# mux-board.net
KiCad netlist of a schematic drawn in EAGLE
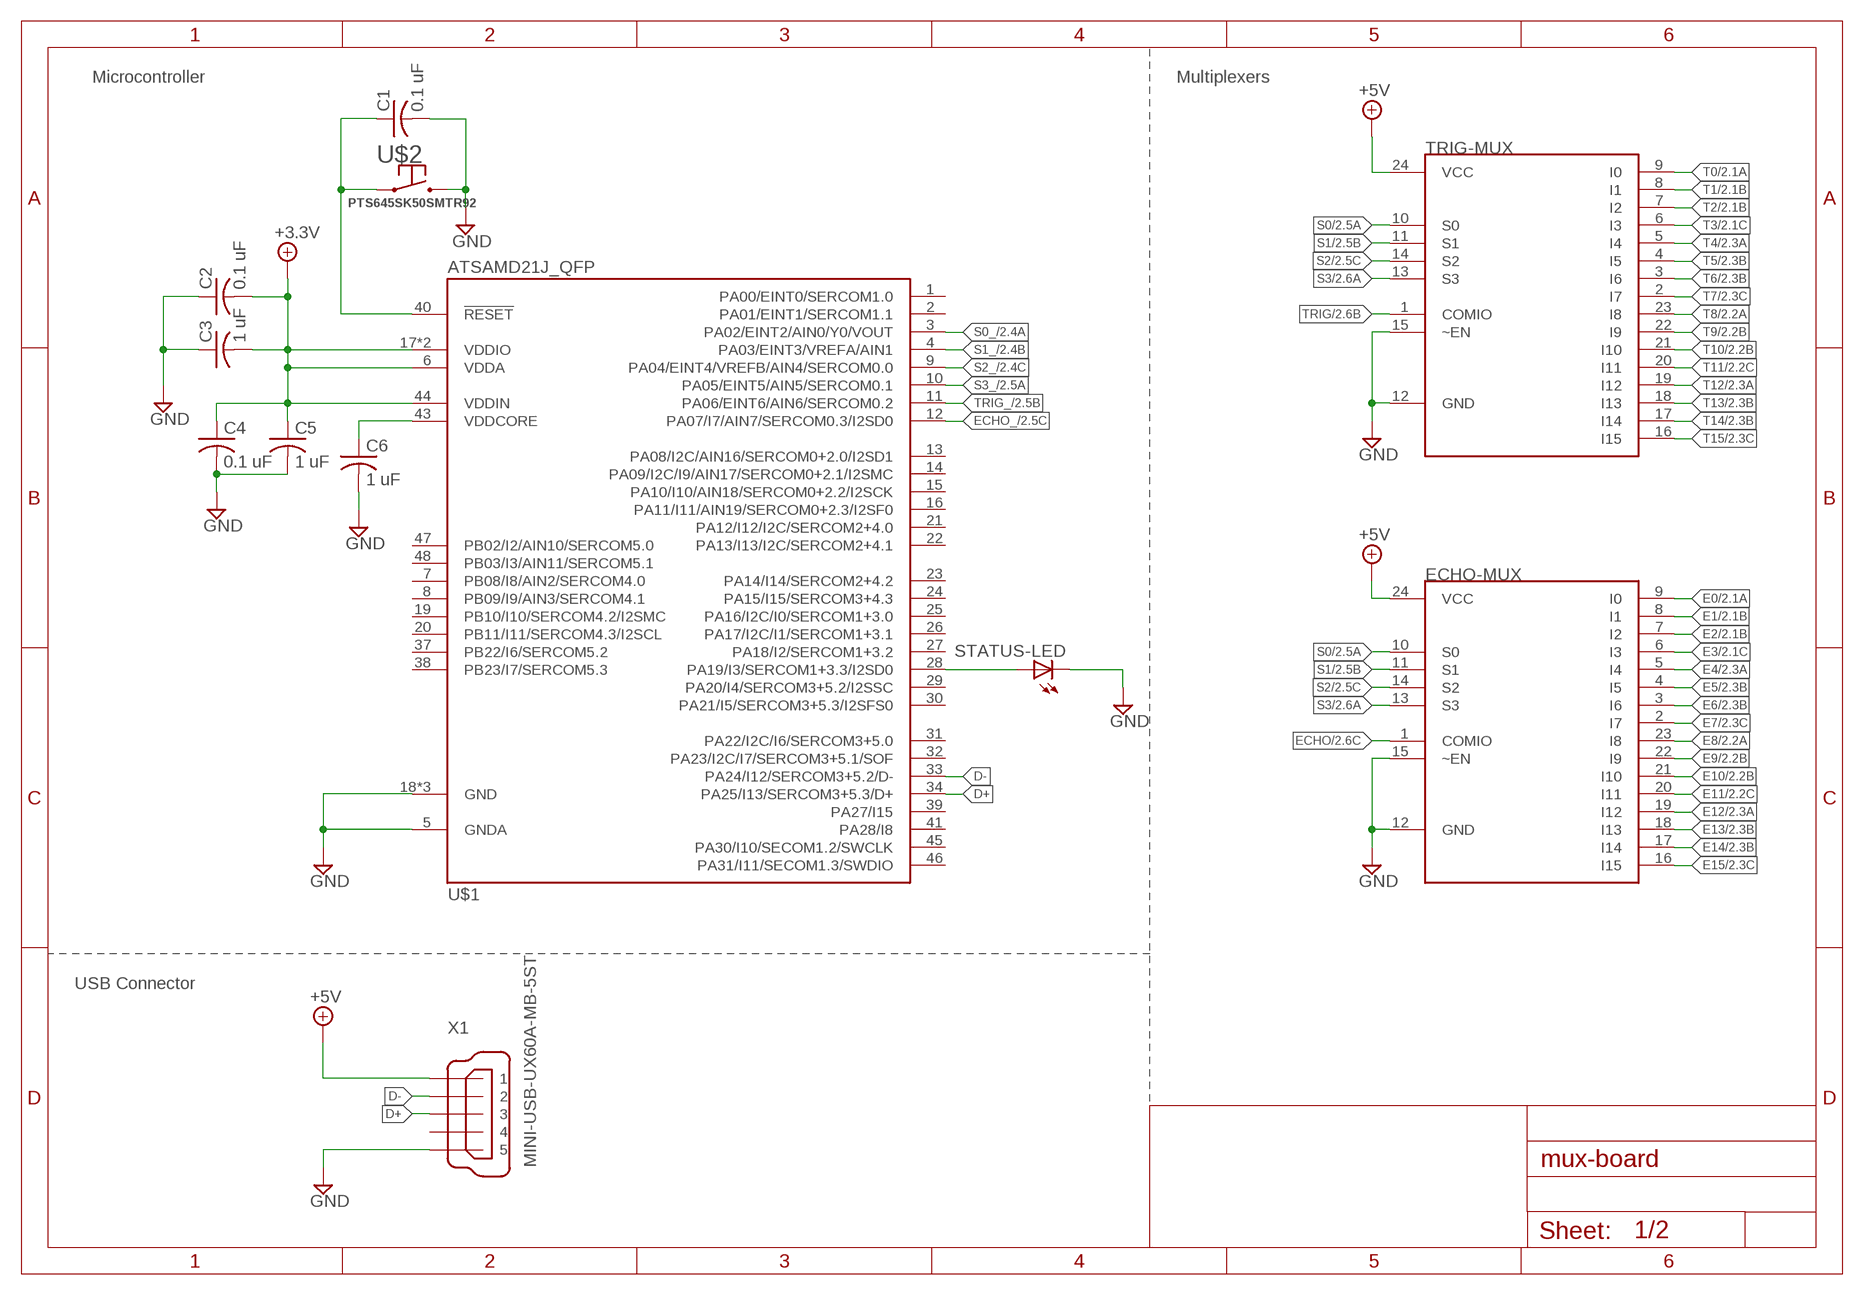
[diagram p0: schematic, sheet 1]
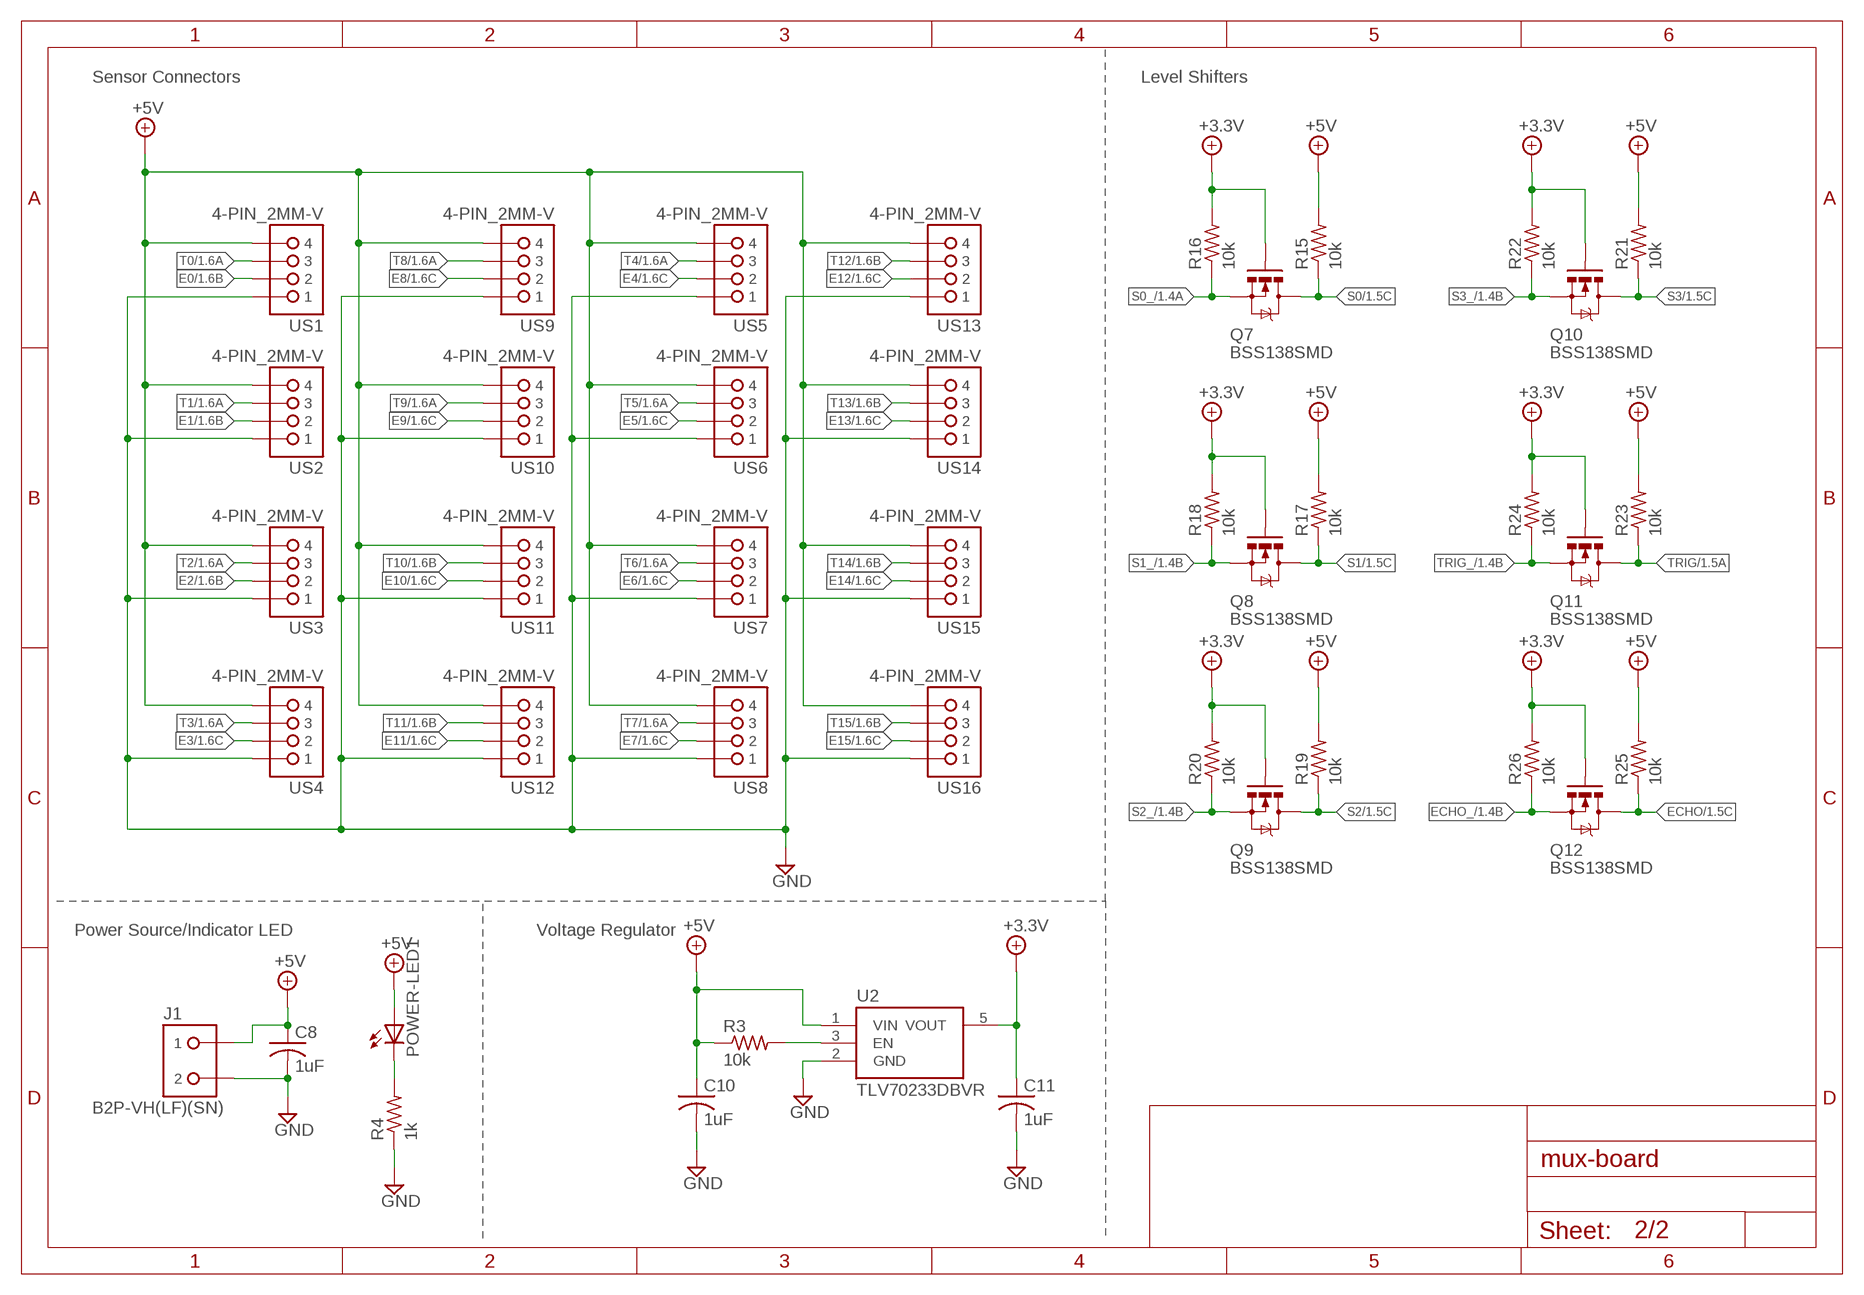
[diagram p1: schematic, sheet 2]

(export (version "E")
  (design (tool "Eeschema 10.0.6"))
  (components
    (comp (ref "C8")
      (value "1uF")
      (footprint "eagle-import:C0603")
      (libsource (lib "eagle-import") (part "C-USC0603"))
    )
    (comp (ref "C10")
      (value "1uF")
      (footprint "eagle-import:C0603")
      (libsource (lib "eagle-import") (part "C-USC0603"))
    )
    (comp (ref "C11")
      (value "1uF")
      (footprint "eagle-import:C0603")
      (libsource (lib "eagle-import") (part "C-USC0603"))
    )
    (comp (ref "J1")
      (value "B2P-VH(LF)(SN)")
      (footprint "eagle-import:B2P")
      (libsource (lib "eagle-import") (part "B2P?-VH(LF)(SN)"))
    )
    (comp (ref "POWER-LED1")
      (value "LEDSML0603")
      (footprint "eagle-import:SML0603")
      (libsource (lib "eagle-import") (part "LEDSML0603"))
    )
    (comp (ref "Q7")
      (value "BSS138SMD")
      (footprint "eagle-import:SPARKFUN_SOT23-3")
      (libsource (lib "eagle-import") (part "BSS138SMD"))
    )
    (comp (ref "Q8")
      (value "BSS138SMD")
      (footprint "eagle-import:SPARKFUN_SOT23-3")
      (libsource (lib "eagle-import") (part "BSS138SMD"))
    )
    (comp (ref "Q9")
      (value "BSS138SMD")
      (footprint "eagle-import:SPARKFUN_SOT23-3")
      (libsource (lib "eagle-import") (part "BSS138SMD"))
    )
    (comp (ref "Q10")
      (value "BSS138SMD")
      (footprint "eagle-import:SPARKFUN_SOT23-3")
      (libsource (lib "eagle-import") (part "BSS138SMD"))
    )
    (comp (ref "Q11")
      (value "BSS138SMD")
      (footprint "eagle-import:SPARKFUN_SOT23-3")
      (libsource (lib "eagle-import") (part "BSS138SMD"))
    )
    (comp (ref "Q12")
      (value "BSS138SMD")
      (footprint "eagle-import:SPARKFUN_SOT23-3")
      (libsource (lib "eagle-import") (part "BSS138SMD"))
    )
    (comp (ref "R3")
      (value "10k")
      (footprint "eagle-import:R0603")
      (libsource (lib "eagle-import") (part "resistor_348_R-US_R0603"))
    )
    (comp (ref "R4")
      (value "1k")
      (footprint "eagle-import:R0603")
      (libsource (lib "eagle-import") (part "resistor_348_R-US_R0603"))
    )
    (comp (ref "R15")
      (value "10k")
      (footprint "eagle-import:R0603")
      (libsource (lib "eagle-import") (part "R-US_R0603"))
    )
    (comp (ref "R16")
      (value "10k")
      (footprint "eagle-import:R0603")
      (libsource (lib "eagle-import") (part "R-US_R0603"))
    )
    (comp (ref "R17")
      (value "10k")
      (footprint "eagle-import:R0603")
      (libsource (lib "eagle-import") (part "R-US_R0603"))
    )
    (comp (ref "R18")
      (value "10k")
      (footprint "eagle-import:R0603")
      (libsource (lib "eagle-import") (part "R-US_R0603"))
    )
    (comp (ref "R19")
      (value "10k")
      (footprint "eagle-import:R0603")
      (libsource (lib "eagle-import") (part "R-US_R0603"))
    )
    (comp (ref "R20")
      (value "10k")
      (footprint "eagle-import:R0603")
      (libsource (lib "eagle-import") (part "R-US_R0603"))
    )
    (comp (ref "R21")
      (value "10k")
      (footprint "eagle-import:R0603")
      (libsource (lib "eagle-import") (part "R-US_R0603"))
    )
    (comp (ref "R22")
      (value "10k")
      (footprint "eagle-import:R0603")
      (libsource (lib "eagle-import") (part "R-US_R0603"))
    )
    (comp (ref "R23")
      (value "10k")
      (footprint "eagle-import:R0603")
      (libsource (lib "eagle-import") (part "R-US_R0603"))
    )
    (comp (ref "R24")
      (value "10k")
      (footprint "eagle-import:R0603")
      (libsource (lib "eagle-import") (part "R-US_R0603"))
    )
    (comp (ref "R25")
      (value "10k")
      (footprint "eagle-import:R0603")
      (libsource (lib "eagle-import") (part "R-US_R0603"))
    )
    (comp (ref "R26")
      (value "10k")
      (footprint "eagle-import:R0603")
      (libsource (lib "eagle-import") (part "R-US_R0603"))
    )
    (comp (ref "U2")
      (value "TLV70233DBVR")
      (footprint "eagle-import:SOT-23-5")
      (libsource (lib "eagle-import") (part "TLV70233DBVR"))
    )
    (comp (ref "US1")
      (value "4-PIN_2MM-V")
      (footprint "eagle-import:2MM-4-V")
      (libsource (lib "eagle-import") (part "4-PIN_2MM-V"))
    )
    (comp (ref "US2")
      (value "4-PIN_2MM-V")
      (footprint "eagle-import:2MM-4-V")
      (libsource (lib "eagle-import") (part "4-PIN_2MM-V"))
    )
    (comp (ref "US3")
      (value "4-PIN_2MM-V")
      (footprint "eagle-import:2MM-4-V")
      (libsource (lib "eagle-import") (part "4-PIN_2MM-V"))
    )
    (comp (ref "US4")
      (value "4-PIN_2MM-V")
      (footprint "eagle-import:2MM-4-V")
      (libsource (lib "eagle-import") (part "4-PIN_2MM-V"))
    )
    (comp (ref "US5")
      (value "4-PIN_2MM-V")
      (footprint "eagle-import:2MM-4-V")
      (libsource (lib "eagle-import") (part "4-PIN_2MM-V"))
    )
    (comp (ref "US6")
      (value "4-PIN_2MM-V")
      (footprint "eagle-import:2MM-4-V")
      (libsource (lib "eagle-import") (part "4-PIN_2MM-V"))
    )
    (comp (ref "US7")
      (value "4-PIN_2MM-V")
      (footprint "eagle-import:2MM-4-V")
      (libsource (lib "eagle-import") (part "4-PIN_2MM-V"))
    )
    (comp (ref "US8")
      (value "4-PIN_2MM-V")
      (footprint "eagle-import:2MM-4-V")
      (libsource (lib "eagle-import") (part "4-PIN_2MM-V"))
    )
    (comp (ref "US9")
      (value "4-PIN_2MM-V")
      (footprint "eagle-import:2MM-4-V")
      (libsource (lib "eagle-import") (part "4-PIN_2MM-V"))
    )
    (comp (ref "US10")
      (value "4-PIN_2MM-V")
      (footprint "eagle-import:2MM-4-V")
      (libsource (lib "eagle-import") (part "4-PIN_2MM-V"))
    )
    (comp (ref "US11")
      (value "4-PIN_2MM-V")
      (footprint "eagle-import:2MM-4-V")
      (libsource (lib "eagle-import") (part "4-PIN_2MM-V"))
    )
    (comp (ref "US12")
      (value "4-PIN_2MM-V")
      (footprint "eagle-import:2MM-4-V")
      (libsource (lib "eagle-import") (part "4-PIN_2MM-V"))
    )
    (comp (ref "US13")
      (value "4-PIN_2MM-V")
      (footprint "eagle-import:2MM-4-V")
      (libsource (lib "eagle-import") (part "4-PIN_2MM-V"))
    )
    (comp (ref "US14")
      (value "4-PIN_2MM-V")
      (footprint "eagle-import:2MM-4-V")
      (libsource (lib "eagle-import") (part "4-PIN_2MM-V"))
    )
    (comp (ref "US15")
      (value "4-PIN_2MM-V")
      (footprint "eagle-import:2MM-4-V")
      (libsource (lib "eagle-import") (part "4-PIN_2MM-V"))
    )
    (comp (ref "US16")
      (value "4-PIN_2MM-V")
      (footprint "eagle-import:2MM-4-V")
      (libsource (lib "eagle-import") (part "4-PIN_2MM-V"))
    )
    (comp (ref "C1")
      (value "0.1 uF")
      (footprint "eagle-import:C0603")
      (libsource (lib "eagle-import") (part "resistor_348_C-USC0603"))
    )
    (comp (ref "C2")
      (value "0.1 uF")
      (footprint "eagle-import:C0603")
      (libsource (lib "eagle-import") (part "resistor_348_C-USC0603"))
    )
    (comp (ref "C3")
      (value "1 uF")
      (footprint "eagle-import:C0603")
      (libsource (lib "eagle-import") (part "resistor_348_C-USC0603"))
    )
    (comp (ref "C4")
      (value "0.1 uF")
      (footprint "eagle-import:C0603")
      (libsource (lib "eagle-import") (part "resistor_348_C-USC0603"))
    )
    (comp (ref "C5")
      (value "1 uF")
      (footprint "eagle-import:C0603")
      (libsource (lib "eagle-import") (part "resistor_348_C-USC0603"))
    )
    (comp (ref "C6")
      (value "1 uF")
      (footprint "eagle-import:C0603")
      (libsource (lib "eagle-import") (part "resistor_348_C-USC0603"))
    )
    (comp (ref "ECHO-MUX")
      (value "CD74HC4067")
      (footprint "eagle-import:SO24R")
      (libsource (lib "eagle-import") (part "CD74HC4067"))
    )
    (comp (ref "STATUS-LED")
      (value "LEDSML0603")
      (footprint "eagle-import:SML0603")
      (libsource (lib "eagle-import") (part "LEDSML0603"))
    )
    (comp (ref "TRIG-MUX")
      (value "CD74HC4067")
      (footprint "eagle-import:SO24R")
      (libsource (lib "eagle-import") (part "CD74HC4067"))
    )
    (comp (ref "U$1")
      (value "ATSAMD21J_QFP")
      (footprint "eagle-import:TQFP48_7MM")
      (libsource (lib "eagle-import") (part "ATSAMD21J_QFP"))
    )
    (comp (ref "U$2")
      (value "PTS645SK50SMTR92")
      (footprint "eagle-import:PTS645SK50SMTR92")
      (libsource (lib "eagle-import") (part "PTS645SK50SMTR92"))
    )
    (comp (ref "X1")
      (value "MINI-USB-UX60A-MB-5ST")
      (footprint "eagle-import:UX60A-MB-5ST")
      (libsource (lib "eagle-import") (part "MINI-USB-UX60A-MB-5ST"))
    )
  )
  (nets
    (net (code "1") (name "+3.3V") (class "Default")
      (node (ref "C11") (pin "1") (pinfunction "1_1") (pintype "passive"))
      (node (ref "C2") (pin "2") (pinfunction "2_2") (pintype "passive"))
      (node (ref "C3") (pin "2") (pinfunction "2_2") (pintype "passive"))
      (node (ref "C4") (pin "1") (pinfunction "1_1") (pintype "passive"))
      (node (ref "C5") (pin "1") (pinfunction "1_1") (pintype "passive"))
      (node (ref "Q10") (pin "1") (pinfunction "G_1") (pintype "passive"))
      (node (ref "Q11") (pin "1") (pinfunction "G_1") (pintype "passive"))
      (node (ref "Q12") (pin "1") (pinfunction "G_1") (pintype "passive"))
      (node (ref "Q7") (pin "1") (pinfunction "G_1") (pintype "passive"))
      (node (ref "Q8") (pin "1") (pinfunction "G_1") (pintype "passive"))
      (node (ref "Q9") (pin "1") (pinfunction "G_1") (pintype "passive"))
      (node (ref "R16") (pin "2") (pinfunction "2_2") (pintype "passive"))
      (node (ref "R18") (pin "2") (pinfunction "2_2") (pintype "passive"))
      (node (ref "R20") (pin "2") (pinfunction "2_2") (pintype "passive"))
      (node (ref "R22") (pin "2") (pinfunction "2_2") (pintype "passive"))
      (node (ref "R24") (pin "2") (pinfunction "2_2") (pintype "passive"))
      (node (ref "R26") (pin "2") (pinfunction "2_2") (pintype "passive"))
      (node (ref "U$1") (pin "17") (pinfunction "VDDIO_17") (pintype "power_in"))
      (node (ref "U$1") (pin "36") (pinfunction "VDDIO_36") (pintype "power_in"))
      (node (ref "U$1") (pin "44") (pinfunction "VDDIN_44") (pintype "power_in"))
      (node (ref "U$1") (pin "6") (pinfunction "VDDA_6") (pintype "power_in"))
      (node (ref "U2") (pin "5") (pinfunction "VOUT_5") (pintype "bidirectional"))
    )
    (net (code "2") (name "+5V") (class "Default")
      (node (ref "C10") (pin "1") (pinfunction "1_1") (pintype "passive"))
      (node (ref "C8") (pin "1") (pinfunction "1_1") (pintype "passive"))
      (node (ref "ECHO-MUX") (pin "24") (pinfunction "VCC_24") (pintype "bidirectional"))
      (node (ref "J1") (pin "1") (pinfunction "1_1") (pintype "bidirectional"))
      (node (ref "POWER-LED1") (pin "A") (pinfunction "A_A") (pintype "passive"))
      (node (ref "R15") (pin "2") (pinfunction "2_2") (pintype "passive"))
      (node (ref "R17") (pin "2") (pinfunction "2_2") (pintype "passive"))
      (node (ref "R19") (pin "2") (pinfunction "2_2") (pintype "passive"))
      (node (ref "R21") (pin "2") (pinfunction "2_2") (pintype "passive"))
      (node (ref "R23") (pin "2") (pinfunction "2_2") (pintype "passive"))
      (node (ref "R25") (pin "2") (pinfunction "2_2") (pintype "passive"))
      (node (ref "R3") (pin "1") (pinfunction "1_1") (pintype "passive"))
      (node (ref "TRIG-MUX") (pin "24") (pinfunction "VCC_24") (pintype "bidirectional"))
      (node (ref "U2") (pin "1") (pinfunction "VIN_1") (pintype "bidirectional"))
      (node (ref "US1") (pin "4") (pinfunction "4_4") (pintype "passive"))
      (node (ref "US10") (pin "4") (pinfunction "4_4") (pintype "passive"))
      (node (ref "US11") (pin "4") (pinfunction "4_4") (pintype "passive"))
      (node (ref "US12") (pin "4") (pinfunction "4_4") (pintype "passive"))
      (node (ref "US13") (pin "4") (pinfunction "4_4") (pintype "passive"))
      (node (ref "US14") (pin "4") (pinfunction "4_4") (pintype "passive"))
      (node (ref "US15") (pin "4") (pinfunction "4_4") (pintype "passive"))
      (node (ref "US16") (pin "4") (pinfunction "4_4") (pintype "passive"))
      (node (ref "US2") (pin "4") (pinfunction "4_4") (pintype "passive"))
      (node (ref "US3") (pin "4") (pinfunction "4_4") (pintype "passive"))
      (node (ref "US4") (pin "4") (pinfunction "4_4") (pintype "passive"))
      (node (ref "US5") (pin "4") (pinfunction "4_4") (pintype "passive"))
      (node (ref "US6") (pin "4") (pinfunction "4_4") (pintype "passive"))
      (node (ref "US7") (pin "4") (pinfunction "4_4") (pintype "passive"))
      (node (ref "US8") (pin "4") (pinfunction "4_4") (pintype "passive"))
      (node (ref "US9") (pin "4") (pinfunction "4_4") (pintype "passive"))
      (node (ref "X1") (pin "1") (pinfunction "1_1") (pintype "input"))
    )
    (net (code "3") (name "D+") (class "Default")
      (node (ref "U$1") (pin "34") (pinfunction "PA25/I13/SERCOM3+5.3/D+_34") (pintype "bidirectional"))
      (node (ref "X1") (pin "3") (pinfunction "3_3") (pintype "input"))
    )
    (net (code "4") (name "D-") (class "Default")
      (node (ref "U$1") (pin "33") (pinfunction "PA24/I12/SERCOM3+5.2/D-_33") (pintype "bidirectional"))
      (node (ref "X1") (pin "2") (pinfunction "2_2") (pintype "input"))
    )
    (net (code "5") (name "E0") (class "Default")
      (node (ref "ECHO-MUX") (pin "9") (pinfunction "I0_9") (pintype "bidirectional"))
      (node (ref "US1") (pin "2") (pinfunction "2_2") (pintype "passive"))
    )
    (net (code "6") (name "E1") (class "Default")
      (node (ref "ECHO-MUX") (pin "8") (pinfunction "I1_8") (pintype "bidirectional"))
      (node (ref "US2") (pin "2") (pinfunction "2_2") (pintype "passive"))
    )
    (net (code "7") (name "E2") (class "Default")
      (node (ref "ECHO-MUX") (pin "7") (pinfunction "I2_7") (pintype "bidirectional"))
      (node (ref "US3") (pin "2") (pinfunction "2_2") (pintype "passive"))
    )
    (net (code "8") (name "E3") (class "Default")
      (node (ref "ECHO-MUX") (pin "6") (pinfunction "I3_6") (pintype "bidirectional"))
      (node (ref "US4") (pin "2") (pinfunction "2_2") (pintype "passive"))
    )
    (net (code "9") (name "E4") (class "Default")
      (node (ref "ECHO-MUX") (pin "5") (pinfunction "I4_5") (pintype "bidirectional"))
      (node (ref "US5") (pin "2") (pinfunction "2_2") (pintype "passive"))
    )
    (net (code "10") (name "E5") (class "Default")
      (node (ref "ECHO-MUX") (pin "4") (pinfunction "I5_4") (pintype "bidirectional"))
      (node (ref "US6") (pin "2") (pinfunction "2_2") (pintype "passive"))
    )
    (net (code "11") (name "E6") (class "Default")
      (node (ref "ECHO-MUX") (pin "3") (pinfunction "I6_3") (pintype "bidirectional"))
      (node (ref "US7") (pin "2") (pinfunction "2_2") (pintype "passive"))
    )
    (net (code "12") (name "E7") (class "Default")
      (node (ref "ECHO-MUX") (pin "2") (pinfunction "I7_2") (pintype "bidirectional"))
      (node (ref "US8") (pin "2") (pinfunction "2_2") (pintype "passive"))
    )
    (net (code "13") (name "E8") (class "Default")
      (node (ref "ECHO-MUX") (pin "23") (pinfunction "I8_23") (pintype "bidirectional"))
      (node (ref "US9") (pin "2") (pinfunction "2_2") (pintype "passive"))
    )
    (net (code "14") (name "E9") (class "Default")
      (node (ref "ECHO-MUX") (pin "22") (pinfunction "I9_22") (pintype "bidirectional"))
      (node (ref "US10") (pin "2") (pinfunction "2_2") (pintype "passive"))
    )
    (net (code "15") (name "E10") (class "Default")
      (node (ref "ECHO-MUX") (pin "21") (pinfunction "I10_21") (pintype "bidirectional"))
      (node (ref "US11") (pin "2") (pinfunction "2_2") (pintype "passive"))
    )
    (net (code "16") (name "E11") (class "Default")
      (node (ref "ECHO-MUX") (pin "20") (pinfunction "I11_20") (pintype "bidirectional"))
      (node (ref "US12") (pin "2") (pinfunction "2_2") (pintype "passive"))
    )
    (net (code "17") (name "E12") (class "Default")
      (node (ref "ECHO-MUX") (pin "19") (pinfunction "I12_19") (pintype "bidirectional"))
      (node (ref "US13") (pin "2") (pinfunction "2_2") (pintype "passive"))
    )
    (net (code "18") (name "E13") (class "Default")
      (node (ref "ECHO-MUX") (pin "18") (pinfunction "I13_18") (pintype "bidirectional"))
      (node (ref "US14") (pin "2") (pinfunction "2_2") (pintype "passive"))
    )
    (net (code "19") (name "E14") (class "Default")
      (node (ref "ECHO-MUX") (pin "17") (pinfunction "I14_17") (pintype "bidirectional"))
      (node (ref "US15") (pin "2") (pinfunction "2_2") (pintype "passive"))
    )
    (net (code "20") (name "E15") (class "Default")
      (node (ref "ECHO-MUX") (pin "16") (pinfunction "I15_16") (pintype "bidirectional"))
      (node (ref "US16") (pin "2") (pinfunction "2_2") (pintype "passive"))
    )
    (net (code "21") (name "ECHO") (class "Default")
      (node (ref "ECHO-MUX") (pin "1") (pinfunction "COMIO_1") (pintype "bidirectional"))
      (node (ref "Q12") (pin "3") (pinfunction "D_3") (pintype "passive"))
      (node (ref "R25") (pin "1") (pinfunction "1_1") (pintype "passive"))
    )
    (net (code "22") (name "ECHO_") (class "Default")
      (node (ref "Q12") (pin "2") (pinfunction "S_2") (pintype "passive"))
      (node (ref "R26") (pin "1") (pinfunction "1_1") (pintype "passive"))
      (node (ref "U$1") (pin "12") (pinfunction "PA07/I7/AIN7/SERCOM0.3/I2SD0_12") (pintype "bidirectional"))
    )
    (net (code "23") (name "GND") (class "Default")
      (node (ref "C1") (pin "2") (pinfunction "2_2") (pintype "passive"))
      (node (ref "C10") (pin "2") (pinfunction "2_2") (pintype "passive"))
      (node (ref "C11") (pin "2") (pinfunction "2_2") (pintype "passive"))
      (node (ref "C2") (pin "1") (pinfunction "1_1") (pintype "passive"))
      (node (ref "C3") (pin "1") (pinfunction "1_1") (pintype "passive"))
      (node (ref "C4") (pin "2") (pinfunction "2_2") (pintype "passive"))
      (node (ref "C5") (pin "2") (pinfunction "2_2") (pintype "passive"))
      (node (ref "C6") (pin "2") (pinfunction "2_2") (pintype "passive"))
      (node (ref "C8") (pin "2") (pinfunction "2_2") (pintype "passive"))
      (node (ref "ECHO-MUX") (pin "12") (pinfunction "GND_12") (pintype "bidirectional"))
      (node (ref "ECHO-MUX") (pin "15") (pinfunction "~{EN}_15") (pintype "bidirectional"))
      (node (ref "J1") (pin "2") (pinfunction "2_2") (pintype "bidirectional"))
      (node (ref "R4") (pin "1") (pinfunction "1_1") (pintype "passive"))
      (node (ref "STATUS-LED") (pin "C") (pinfunction "C_C") (pintype "passive"))
      (node (ref "TRIG-MUX") (pin "12") (pinfunction "GND_12") (pintype "bidirectional"))
      (node (ref "TRIG-MUX") (pin "15") (pinfunction "~{EN}_15") (pintype "bidirectional"))
      (node (ref "U$1") (pin "18") (pinfunction "GND_18") (pintype "power_in"))
      (node (ref "U$1") (pin "35") (pinfunction "GND_35") (pintype "power_in"))
      (node (ref "U$1") (pin "42") (pinfunction "GND_42") (pintype "power_in"))
      (node (ref "U$1") (pin "5") (pinfunction "GNDA_5") (pintype "power_in"))
      (node (ref "U$2") (pin "3") (pinfunction "2_3") (pintype "passive"))
      (node (ref "U$2") (pin "4") (pinfunction "2_4") (pintype "passive"))
      (node (ref "U2") (pin "2") (pinfunction "GND_2") (pintype "bidirectional"))
      (node (ref "US1") (pin "1") (pinfunction "1_1") (pintype "passive"))
      (node (ref "US10") (pin "1") (pinfunction "1_1") (pintype "passive"))
      (node (ref "US11") (pin "1") (pinfunction "1_1") (pintype "passive"))
      (node (ref "US12") (pin "1") (pinfunction "1_1") (pintype "passive"))
      (node (ref "US13") (pin "1") (pinfunction "1_1") (pintype "passive"))
      (node (ref "US14") (pin "1") (pinfunction "1_1") (pintype "passive"))
      (node (ref "US15") (pin "1") (pinfunction "1_1") (pintype "passive"))
      (node (ref "US16") (pin "1") (pinfunction "1_1") (pintype "passive"))
      (node (ref "US2") (pin "1") (pinfunction "1_1") (pintype "passive"))
      (node (ref "US3") (pin "1") (pinfunction "1_1") (pintype "passive"))
      (node (ref "US4") (pin "1") (pinfunction "1_1") (pintype "passive"))
      (node (ref "US5") (pin "1") (pinfunction "1_1") (pintype "passive"))
      (node (ref "US6") (pin "1") (pinfunction "1_1") (pintype "passive"))
      (node (ref "US7") (pin "1") (pinfunction "1_1") (pintype "passive"))
      (node (ref "US8") (pin "1") (pinfunction "1_1") (pintype "passive"))
      (node (ref "US9") (pin "1") (pinfunction "1_1") (pintype "passive"))
      (node (ref "X1") (pin "5") (pinfunction "5_5") (pintype "input"))
    )
    (net (code "24") (name "Net-(POWER-LED1-PadC)") (class "Default")
      (node (ref "POWER-LED1") (pin "C") (pinfunction "C_C") (pintype "passive"))
      (node (ref "R4") (pin "2") (pinfunction "2_2") (pintype "passive"))
    )
    (net (code "25") (name "Net-(U$1-PA19{slash}I3{slash}SERCOM1+3.3{slash}I2SD0)") (class "Default")
      (node (ref "STATUS-LED") (pin "A") (pinfunction "A_A") (pintype "passive"))
      (node (ref "U$1") (pin "28") (pinfunction "PA19/I3/SERCOM1+3.3/I2SD0_28") (pintype "bidirectional"))
    )
    (net (code "26") (name "Net-(U$1-VDDCORE)") (class "Default")
      (node (ref "C6") (pin "1") (pinfunction "1_1") (pintype "passive"))
      (node (ref "U$1") (pin "43") (pinfunction "VDDCORE_43") (pintype "power_in"))
    )
    (net (code "27") (name "Net-(U$1-~{RESET})") (class "Default")
      (node (ref "C1") (pin "1") (pinfunction "1_1") (pintype "passive"))
      (node (ref "U$1") (pin "40") (pinfunction "~{RESET}_40") (pintype "bidirectional"))
      (node (ref "U$2") (pin "1") (pinfunction "1_1") (pintype "passive"))
      (node (ref "U$2") (pin "2") (pinfunction "1_2") (pintype "passive"))
    )
    (net (code "28") (name "Net-(U2-EN)") (class "Default")
      (node (ref "R3") (pin "2") (pinfunction "2_2") (pintype "passive"))
      (node (ref "U2") (pin "3") (pinfunction "EN_3") (pintype "bidirectional"))
    )
    (net (code "29") (name "S0") (class "Default")
      (node (ref "ECHO-MUX") (pin "10") (pinfunction "S0_10") (pintype "bidirectional"))
      (node (ref "Q7") (pin "3") (pinfunction "D_3") (pintype "passive"))
      (node (ref "R15") (pin "1") (pinfunction "1_1") (pintype "passive"))
      (node (ref "TRIG-MUX") (pin "10") (pinfunction "S0_10") (pintype "bidirectional"))
    )
    (net (code "30") (name "S0_") (class "Default")
      (node (ref "Q7") (pin "2") (pinfunction "S_2") (pintype "passive"))
      (node (ref "R16") (pin "1") (pinfunction "1_1") (pintype "passive"))
      (node (ref "U$1") (pin "3") (pinfunction "PA02/EINT2/AIN0/Y0/VOUT_3") (pintype "bidirectional"))
    )
    (net (code "31") (name "S1") (class "Default")
      (node (ref "ECHO-MUX") (pin "11") (pinfunction "S1_11") (pintype "bidirectional"))
      (node (ref "Q8") (pin "3") (pinfunction "D_3") (pintype "passive"))
      (node (ref "R17") (pin "1") (pinfunction "1_1") (pintype "passive"))
      (node (ref "TRIG-MUX") (pin "11") (pinfunction "S1_11") (pintype "bidirectional"))
    )
    (net (code "32") (name "S1_") (class "Default")
      (node (ref "Q8") (pin "2") (pinfunction "S_2") (pintype "passive"))
      (node (ref "R18") (pin "1") (pinfunction "1_1") (pintype "passive"))
      (node (ref "U$1") (pin "4") (pinfunction "PA03/EINT3/VREFA/AIN1_4") (pintype "bidirectional"))
    )
    (net (code "33") (name "S2") (class "Default")
      (node (ref "ECHO-MUX") (pin "14") (pinfunction "S2_14") (pintype "bidirectional"))
      (node (ref "Q9") (pin "3") (pinfunction "D_3") (pintype "passive"))
      (node (ref "R19") (pin "1") (pinfunction "1_1") (pintype "passive"))
      (node (ref "TRIG-MUX") (pin "14") (pinfunction "S2_14") (pintype "bidirectional"))
    )
    (net (code "34") (name "S2_") (class "Default")
      (node (ref "Q9") (pin "2") (pinfunction "S_2") (pintype "passive"))
      (node (ref "R20") (pin "1") (pinfunction "1_1") (pintype "passive"))
      (node (ref "U$1") (pin "9") (pinfunction "PA04/EINT4/VREFB/AIN4/SERCOM0.0_9") (pintype "bidirectional"))
    )
    (net (code "35") (name "S3") (class "Default")
      (node (ref "ECHO-MUX") (pin "13") (pinfunction "S3_13") (pintype "bidirectional"))
      (node (ref "Q10") (pin "3") (pinfunction "D_3") (pintype "passive"))
      (node (ref "R21") (pin "1") (pinfunction "1_1") (pintype "passive"))
      (node (ref "TRIG-MUX") (pin "13") (pinfunction "S3_13") (pintype "bidirectional"))
    )
    (net (code "36") (name "S3_") (class "Default")
      (node (ref "Q10") (pin "2") (pinfunction "S_2") (pintype "passive"))
      (node (ref "R22") (pin "1") (pinfunction "1_1") (pintype "passive"))
      (node (ref "U$1") (pin "10") (pinfunction "PA05/EINT5/AIN5/SERCOM0.1_10") (pintype "bidirectional"))
    )
    (net (code "37") (name "T0") (class "Default")
      (node (ref "TRIG-MUX") (pin "9") (pinfunction "I0_9") (pintype "bidirectional"))
      (node (ref "US1") (pin "3") (pinfunction "3_3") (pintype "passive"))
    )
    (net (code "38") (name "T1") (class "Default")
      (node (ref "TRIG-MUX") (pin "8") (pinfunction "I1_8") (pintype "bidirectional"))
      (node (ref "US2") (pin "3") (pinfunction "3_3") (pintype "passive"))
    )
    (net (code "39") (name "T2") (class "Default")
      (node (ref "TRIG-MUX") (pin "7") (pinfunction "I2_7") (pintype "bidirectional"))
      (node (ref "US3") (pin "3") (pinfunction "3_3") (pintype "passive"))
    )
    (net (code "40") (name "T3") (class "Default")
      (node (ref "TRIG-MUX") (pin "6") (pinfunction "I3_6") (pintype "bidirectional"))
      (node (ref "US4") (pin "3") (pinfunction "3_3") (pintype "passive"))
    )
    (net (code "41") (name "T4") (class "Default")
      (node (ref "TRIG-MUX") (pin "5") (pinfunction "I4_5") (pintype "bidirectional"))
      (node (ref "US5") (pin "3") (pinfunction "3_3") (pintype "passive"))
    )
    (net (code "42") (name "T5") (class "Default")
      (node (ref "TRIG-MUX") (pin "4") (pinfunction "I5_4") (pintype "bidirectional"))
      (node (ref "US6") (pin "3") (pinfunction "3_3") (pintype "passive"))
    )
    (net (code "43") (name "T6") (class "Default")
      (node (ref "TRIG-MUX") (pin "3") (pinfunction "I6_3") (pintype "bidirectional"))
      (node (ref "US7") (pin "3") (pinfunction "3_3") (pintype "passive"))
    )
    (net (code "44") (name "T7") (class "Default")
      (node (ref "TRIG-MUX") (pin "2") (pinfunction "I7_2") (pintype "bidirectional"))
      (node (ref "US8") (pin "3") (pinfunction "3_3") (pintype "passive"))
    )
    (net (code "45") (name "T8") (class "Default")
      (node (ref "TRIG-MUX") (pin "23") (pinfunction "I8_23") (pintype "bidirectional"))
      (node (ref "US9") (pin "3") (pinfunction "3_3") (pintype "passive"))
    )
    (net (code "46") (name "T9") (class "Default")
      (node (ref "TRIG-MUX") (pin "22") (pinfunction "I9_22") (pintype "bidirectional"))
      (node (ref "US10") (pin "3") (pinfunction "3_3") (pintype "passive"))
    )
    (net (code "47") (name "T10") (class "Default")
      (node (ref "TRIG-MUX") (pin "21") (pinfunction "I10_21") (pintype "bidirectional"))
      (node (ref "US11") (pin "3") (pinfunction "3_3") (pintype "passive"))
    )
    (net (code "48") (name "T11") (class "Default")
      (node (ref "TRIG-MUX") (pin "20") (pinfunction "I11_20") (pintype "bidirectional"))
      (node (ref "US12") (pin "3") (pinfunction "3_3") (pintype "passive"))
    )
    (net (code "49") (name "T12") (class "Default")
      (node (ref "TRIG-MUX") (pin "19") (pinfunction "I12_19") (pintype "bidirectional"))
      (node (ref "US13") (pin "3") (pinfunction "3_3") (pintype "passive"))
    )
    (net (code "50") (name "T13") (class "Default")
      (node (ref "TRIG-MUX") (pin "18") (pinfunction "I13_18") (pintype "bidirectional"))
      (node (ref "US14") (pin "3") (pinfunction "3_3") (pintype "passive"))
    )
    (net (code "51") (name "T14") (class "Default")
      (node (ref "TRIG-MUX") (pin "17") (pinfunction "I14_17") (pintype "bidirectional"))
      (node (ref "US15") (pin "3") (pinfunction "3_3") (pintype "passive"))
    )
    (net (code "52") (name "T15") (class "Default")
      (node (ref "TRIG-MUX") (pin "16") (pinfunction "I15_16") (pintype "bidirectional"))
      (node (ref "US16") (pin "3") (pinfunction "3_3") (pintype "passive"))
    )
    (net (code "53") (name "TRIG") (class "Default")
      (node (ref "Q11") (pin "3") (pinfunction "D_3") (pintype "passive"))
      (node (ref "R23") (pin "1") (pinfunction "1_1") (pintype "passive"))
      (node (ref "TRIG-MUX") (pin "1") (pinfunction "COMIO_1") (pintype "bidirectional"))
    )
    (net (code "54") (name "TRIG_") (class "Default")
      (node (ref "Q11") (pin "2") (pinfunction "S_2") (pintype "passive"))
      (node (ref "R24") (pin "1") (pinfunction "1_1") (pintype "passive"))
      (node (ref "U$1") (pin "11") (pinfunction "PA06/EINT6/AIN6/SERCOM0.2_11") (pintype "bidirectional"))
    )
    (net (code "55") (name "unconnected-(U$1-PA00{slash}EINT0{slash}SERCOM1.0-Pad1)") (class "Default")
      (node (ref "U$1") (pin "1") (pinfunction "PA00/EINT0/SERCOM1.0_1") (pintype "bidirectional"))
    )
    (net (code "56") (name "unconnected-(U$1-PA01{slash}EINT1{slash}SERCOM1.1-Pad2)") (class "Default")
      (node (ref "U$1") (pin "2") (pinfunction "PA01/EINT1/SERCOM1.1_2") (pintype "bidirectional"))
    )
    (net (code "57") (name "unconnected-(U$1-PA08{slash}I2C{slash}AIN16{slash}SERCOM0+2.0{slash}I2SD1-Pad13)") (class "Default")
      (node (ref "U$1") (pin "13") (pinfunction "PA08/I2C/AIN16/SERCOM0+2.0/I2SD1_13") (pintype "bidirectional"))
    )
    (net (code "58") (name "unconnected-(U$1-PA09{slash}I2C{slash}I9{slash}AIN17{slash}SERCOM0+2.1{slash}I2SMC-Pad14)") (class "Default")
      (node (ref "U$1") (pin "14") (pinfunction "PA09/I2C/I9/AIN17/SERCOM0+2.1/I2SMC_14") (pintype "bidirectional"))
    )
    (net (code "59") (name "unconnected-(U$1-PA10{slash}I10{slash}AIN18{slash}SERCOM0+2.2{slash}I2SCK-Pad15)") (class "Default")
      (node (ref "U$1") (pin "15") (pinfunction "PA10/I10/AIN18/SERCOM0+2.2/I2SCK_15") (pintype "bidirectional"))
    )
    (net (code "60") (name "unconnected-(U$1-PA11{slash}I11{slash}AIN19{slash}SERCOM0+2.3{slash}I2SF0-Pad16)") (class "Default")
      (node (ref "U$1") (pin "16") (pinfunction "PA11/I11/AIN19/SERCOM0+2.3/I2SF0_16") (pintype "bidirectional"))
    )
    (net (code "61") (name "unconnected-(U$1-PA12{slash}I12{slash}I2C{slash}SERCOM2+4.0-Pad21)") (class "Default")
      (node (ref "U$1") (pin "21") (pinfunction "PA12/I12/I2C/SERCOM2+4.0_21") (pintype "bidirectional"))
    )
    (net (code "62") (name "unconnected-(U$1-PA13{slash}I13{slash}I2C{slash}SERCOM2+4.1-Pad22)") (class "Default")
      (node (ref "U$1") (pin "22") (pinfunction "PA13/I13/I2C/SERCOM2+4.1_22") (pintype "bidirectional"))
    )
    (net (code "63") (name "unconnected-(U$1-PA14{slash}I14{slash}SERCOM2+4.2-Pad23)") (class "Default")
      (node (ref "U$1") (pin "23") (pinfunction "PA14/I14/SERCOM2+4.2_23") (pintype "bidirectional"))
    )
    (net (code "64") (name "unconnected-(U$1-PA15{slash}I15{slash}SERCOM3+4.3-Pad24)") (class "Default")
      (node (ref "U$1") (pin "24") (pinfunction "PA15/I15/SERCOM3+4.3_24") (pintype "bidirectional"))
    )
    (net (code "65") (name "unconnected-(U$1-PA16{slash}I2C{slash}I0{slash}SERCOM1+3.0-Pad25)") (class "Default")
      (node (ref "U$1") (pin "25") (pinfunction "PA16/I2C/I0/SERCOM1+3.0_25") (pintype "bidirectional"))
    )
    (net (code "66") (name "unconnected-(U$1-PA17{slash}I2C{slash}I1{slash}SERCOM1+3.1-Pad26)") (class "Default")
      (node (ref "U$1") (pin "26") (pinfunction "PA17/I2C/I1/SERCOM1+3.1_26") (pintype "bidirectional"))
    )
    (net (code "67") (name "unconnected-(U$1-PA18{slash}I2{slash}SERCOM1+3.2-Pad27)") (class "Default")
      (node (ref "U$1") (pin "27") (pinfunction "PA18/I2/SERCOM1+3.2_27") (pintype "bidirectional"))
    )
    (net (code "68") (name "unconnected-(U$1-PA20{slash}I4{slash}SERCOM3+5.2{slash}I2SSC-Pad29)") (class "Default")
      (node (ref "U$1") (pin "29") (pinfunction "PA20/I4/SERCOM3+5.2/I2SSC_29") (pintype "bidirectional"))
    )
    (net (code "69") (name "unconnected-(U$1-PA21{slash}I5{slash}SERCOM3+5.3{slash}I2SFS0-Pad30)") (class "Default")
      (node (ref "U$1") (pin "30") (pinfunction "PA21/I5/SERCOM3+5.3/I2SFS0_30") (pintype "bidirectional"))
    )
    (net (code "70") (name "unconnected-(U$1-PA22{slash}I2C{slash}I6{slash}SERCOM3+5.0-Pad31)") (class "Default")
      (node (ref "U$1") (pin "31") (pinfunction "PA22/I2C/I6/SERCOM3+5.0_31") (pintype "bidirectional"))
    )
    (net (code "71") (name "unconnected-(U$1-PA23{slash}I2C{slash}I7{slash}SERCOM3+5.1{slash}SOF-Pad32)") (class "Default")
      (node (ref "U$1") (pin "32") (pinfunction "PA23/I2C/I7/SERCOM3+5.1/SOF_32") (pintype "bidirectional"))
    )
    (net (code "72") (name "unconnected-(U$1-PA27{slash}I15-Pad39)") (class "Default")
      (node (ref "U$1") (pin "39") (pinfunction "PA27/I15_39") (pintype "bidirectional"))
    )
    (net (code "73") (name "unconnected-(U$1-PA28{slash}I8-Pad41)") (class "Default")
      (node (ref "U$1") (pin "41") (pinfunction "PA28/I8_41") (pintype "bidirectional"))
    )
    (net (code "74") (name "unconnected-(U$1-PA30{slash}I10{slash}SECOM1.2{slash}SWCLK-Pad45)") (class "Default")
      (node (ref "U$1") (pin "45") (pinfunction "PA30/I10/SECOM1.2/SWCLK_45") (pintype "bidirectional"))
    )
    (net (code "75") (name "unconnected-(U$1-PA31{slash}I11{slash}SECOM1.3{slash}SWDIO-Pad46)") (class "Default")
      (node (ref "U$1") (pin "46") (pinfunction "PA31/I11/SECOM1.3/SWDIO_46") (pintype "bidirectional"))
    )
    (net (code "76") (name "unconnected-(U$1-PB02{slash}I2{slash}AIN10{slash}SERCOM5.0-Pad47)") (class "Default")
      (node (ref "U$1") (pin "47") (pinfunction "PB02/I2/AIN10/SERCOM5.0_47") (pintype "bidirectional"))
    )
    (net (code "77") (name "unconnected-(U$1-PB03{slash}I3{slash}AIN11{slash}SERCOM5.1-Pad48)") (class "Default")
      (node (ref "U$1") (pin "48") (pinfunction "PB03/I3/AIN11/SERCOM5.1_48") (pintype "bidirectional"))
    )
    (net (code "78") (name "unconnected-(U$1-PB08{slash}I8{slash}AIN2{slash}SERCOM4.0-Pad7)") (class "Default")
      (node (ref "U$1") (pin "7") (pinfunction "PB08/I8/AIN2/SERCOM4.0_7") (pintype "bidirectional"))
    )
    (net (code "79") (name "unconnected-(U$1-PB09{slash}I9{slash}AIN3{slash}SERCOM4.1-Pad8)") (class "Default")
      (node (ref "U$1") (pin "8") (pinfunction "PB09/I9/AIN3/SERCOM4.1_8") (pintype "bidirectional"))
    )
    (net (code "80") (name "unconnected-(U$1-PB10{slash}I10{slash}SERCOM4.2{slash}I2SMC-Pad19)") (class "Default")
      (node (ref "U$1") (pin "19") (pinfunction "PB10/I10/SERCOM4.2/I2SMC_19") (pintype "bidirectional"))
    )
    (net (code "81") (name "unconnected-(U$1-PB11{slash}I11{slash}SERCOM4.3{slash}I2SCL-Pad20)") (class "Default")
      (node (ref "U$1") (pin "20") (pinfunction "PB11/I11/SERCOM4.3/I2SCL_20") (pintype "bidirectional"))
    )
    (net (code "82") (name "unconnected-(U$1-PB22{slash}I6{slash}SERCOM5.2-Pad37)") (class "Default")
      (node (ref "U$1") (pin "37") (pinfunction "PB22/I6/SERCOM5.2_37") (pintype "bidirectional"))
    )
    (net (code "83") (name "unconnected-(U$1-PB23{slash}I7{slash}SERCOM5.3-Pad38)") (class "Default")
      (node (ref "U$1") (pin "38") (pinfunction "PB23/I7/SERCOM5.3_38") (pintype "bidirectional"))
    )
    (net (code "84") (name "unconnected-(X1-Pad4)") (class "Default")
      (node (ref "X1") (pin "4") (pinfunction "4_4") (pintype "input"))
    )
  )
)
